# controller.net
KiCad netlist of a schematic drawn in EAGLE
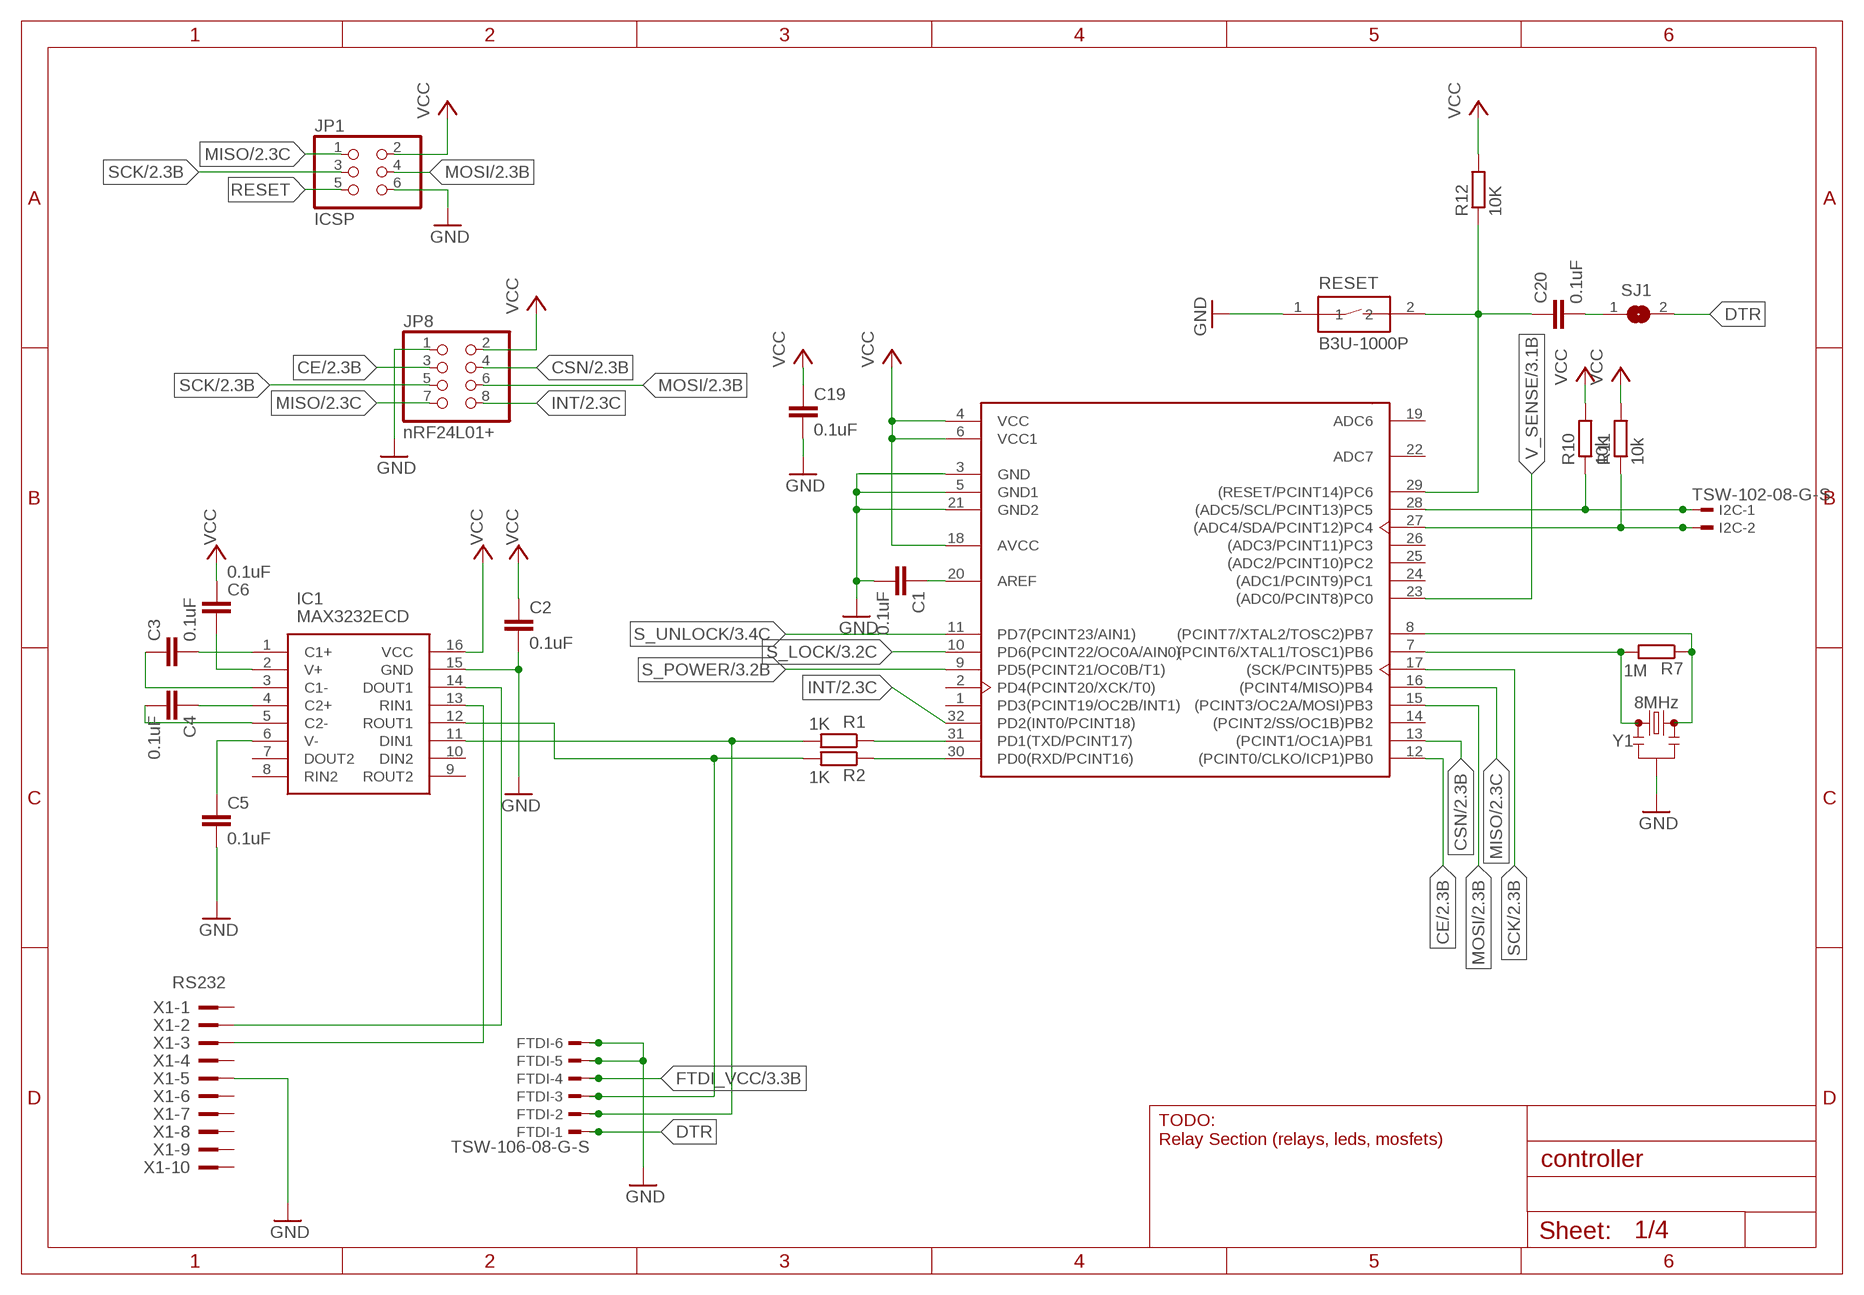
[diagram p0: schematic, sheet 1]
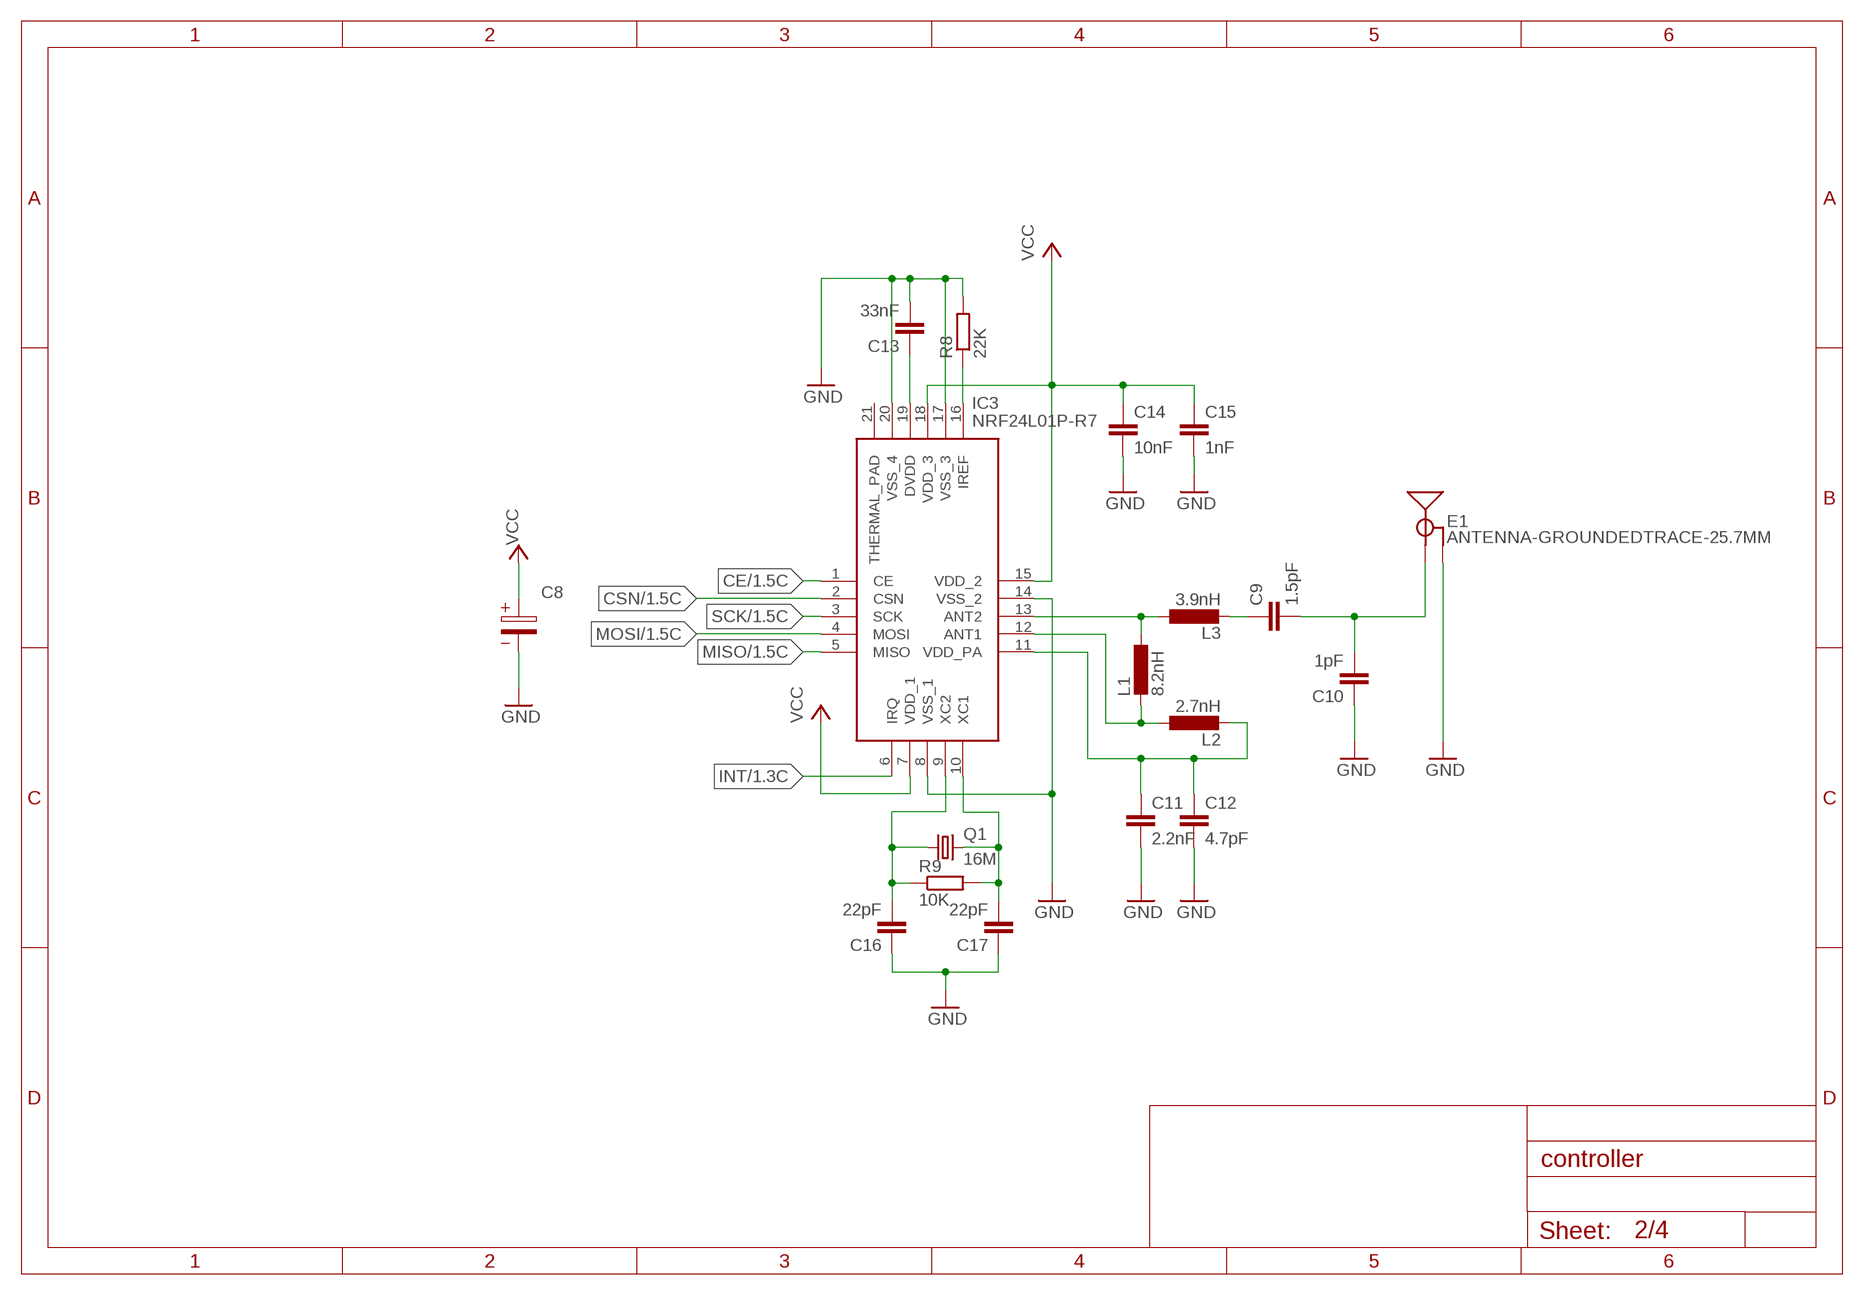
[diagram p1: schematic, sheet 2]
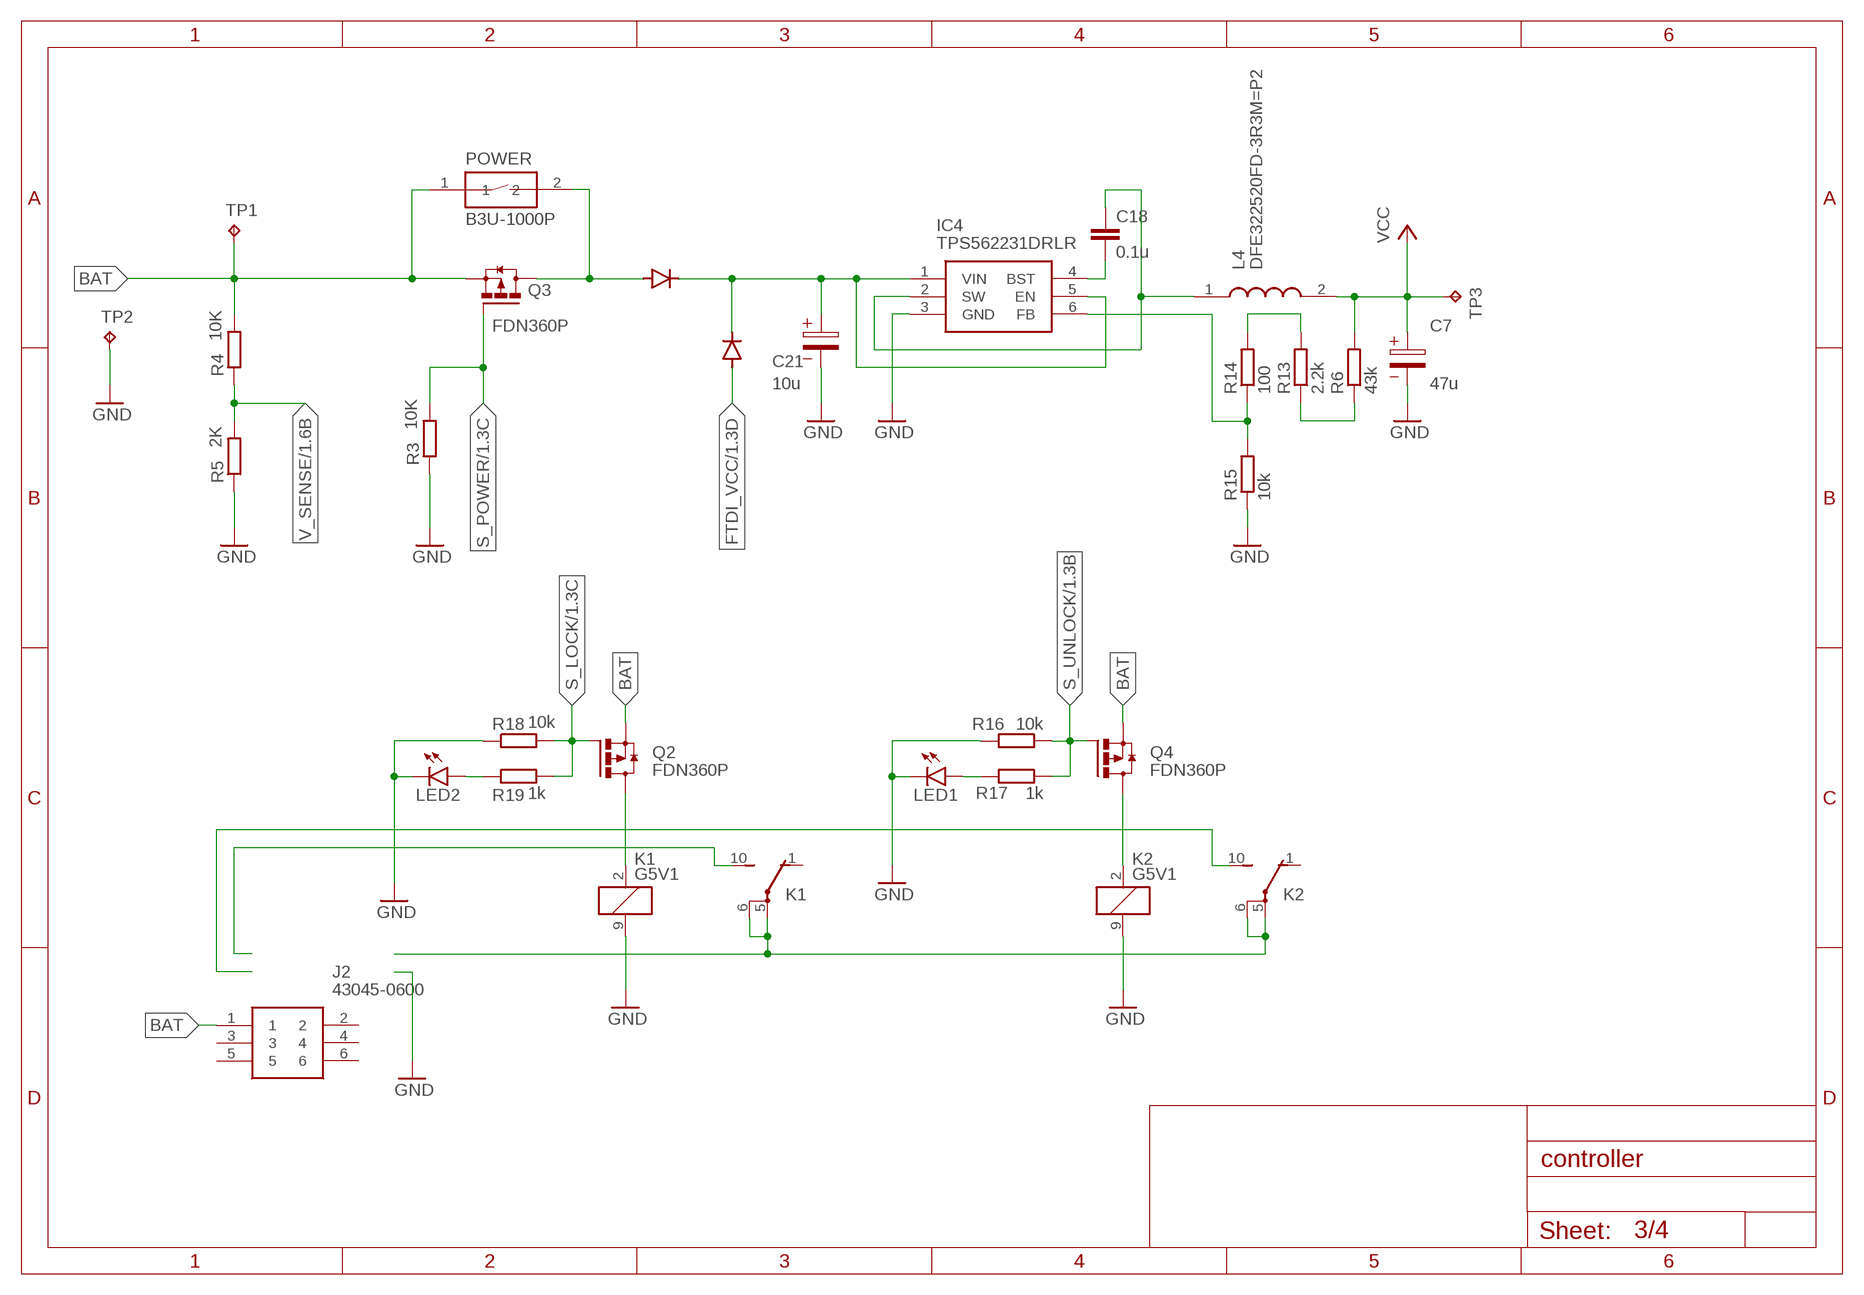
[diagram p2: schematic, sheet 3]
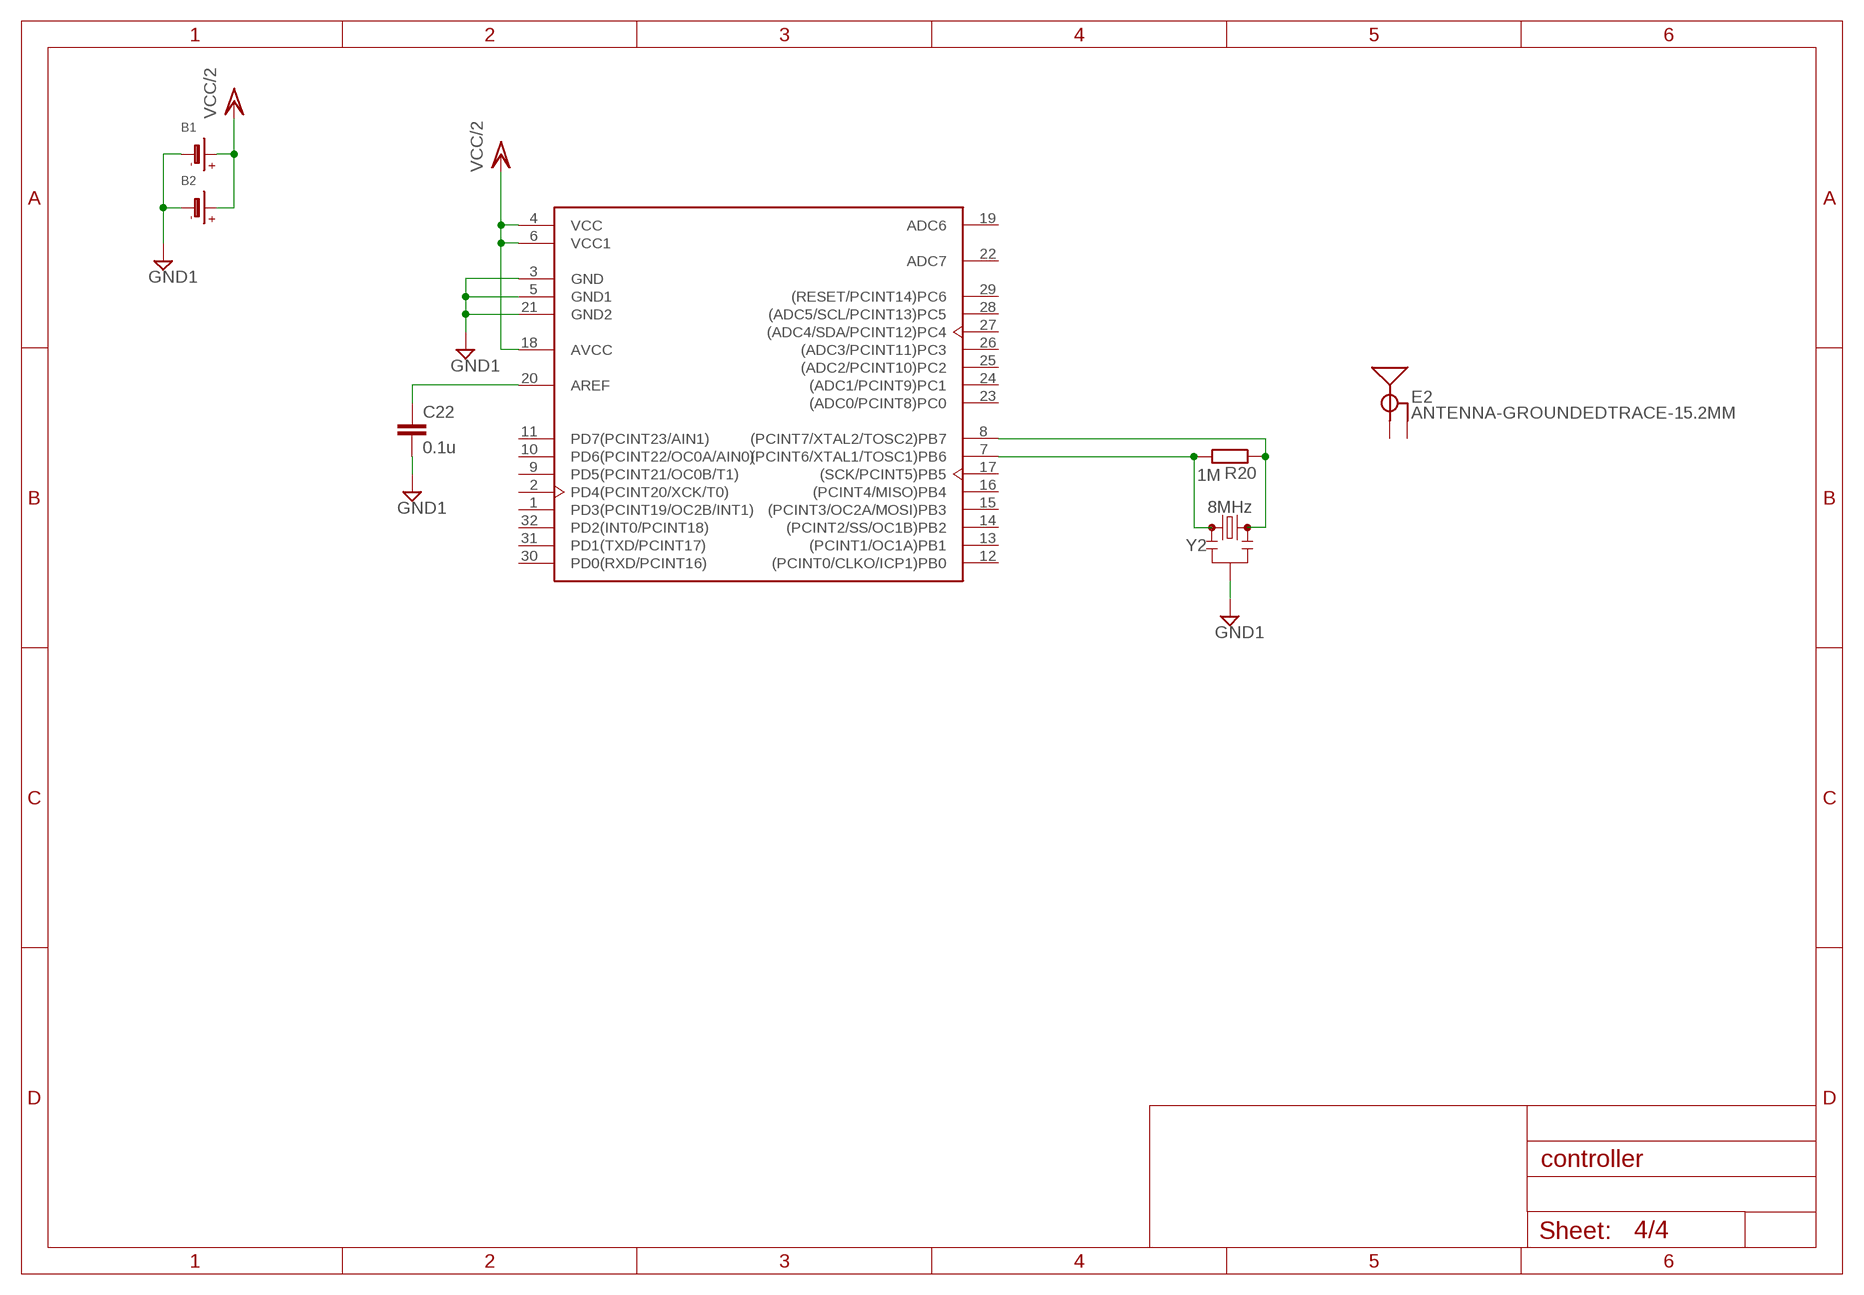
[diagram p3: schematic, sheet 4]

(export (version "E")
  (design (tool "Eeschema 10.0.6"))
  (components
    (comp (ref "B1")
      (value "BATTERYCR2032_BAT-HLD-001")
      (footprint "eagle-import:CR2032_SMT_BAT-HLD-001")
      (libsource (lib "eagle-import") (part "BATTERYCR2032_BAT-HLD-001"))
    )
    (comp (ref "B2")
      (value "BATTERYCR2032_BAT-HLD-001")
      (footprint "eagle-import:CR2032_SMT_BAT-HLD-001")
      (libsource (lib "eagle-import") (part "BATTERYCR2032_BAT-HLD-001"))
    )
    (comp (ref "C22")
      (value "0.1u")
      (footprint "eagle-import:C0805")
      (libsource (lib "eagle-import") (part "C-EUC0805"))
    )
    (comp (ref "E2")
      (value "ANTENNA-GROUNDEDTRACE-15.2MM")
      (footprint "eagle-import:TRACE_ANTENNA_2.4GHZ_15.2MM")
      (libsource (lib "eagle-import") (part "ANTENNA-GROUNDEDTRACE-15.2MM"))
    )
    (comp (ref "R20")
      (value "1M")
      (footprint "eagle-import:R0805")
      (libsource (lib "eagle-import") (part "R-EU_R0805"))
    )
    (comp (ref "U1")
      (value "ATMEGA328P-AU")
      (footprint "eagle-import:TQFP-32")
      (fields
        (field (name "DIGIKEY_PART_NUMBER") "ATMEGA328P-AU-ND")
        (field (name "MANUFACTURER") "Microchip Technology")
        (field (name "CREATED_BY") "PCBLayout.com")
      )
      (libsource (lib "eagle-import") (part "ATMEGA328P-AU"))
    )
    (comp (ref "Y2")
      (value "8MHz")
      (footprint "eagle-import:RESONATOR-SMD-3.2X1.3")
      (libsource (lib "eagle-import") (part "RESONATOR-8MHZSMD_3.2X1.3"))
    )
    (comp (ref "C8")
      (value "WCAP-ASLI_8X6,5_865080149011")
      (footprint "eagle-import:4.2X1.9X2.8(BXCXA)")
      (libsource (lib "eagle-import") (part "WCAP-ASLI_865080149011_8X6,5"))
    )
    (comp (ref "C9")
      (value "1.5pF")
      (footprint "eagle-import:C0805")
      (libsource (lib "eagle-import") (part "resistor_348_C-EUC0805"))
    )
    (comp (ref "C10")
      (value "1pF")
      (footprint "eagle-import:C0805")
      (libsource (lib "eagle-import") (part "resistor_348_C-EUC0805"))
    )
    (comp (ref "C11")
      (value "2.2nF")
      (footprint "eagle-import:C0805")
      (libsource (lib "eagle-import") (part "resistor_348_C-EUC0805"))
    )
    (comp (ref "C12")
      (value "4.7pF")
      (footprint "eagle-import:C0805")
      (libsource (lib "eagle-import") (part "resistor_348_C-EUC0805"))
    )
    (comp (ref "C13")
      (value "33nF")
      (footprint "eagle-import:C0805")
      (libsource (lib "eagle-import") (part "resistor_348_C-EUC0805"))
    )
    (comp (ref "C14")
      (value "10nF")
      (footprint "eagle-import:C0805")
      (libsource (lib "eagle-import") (part "resistor_348_C-EUC0805"))
    )
    (comp (ref "C15")
      (value "1nF")
      (footprint "eagle-import:C0805")
      (libsource (lib "eagle-import") (part "resistor_348_C-EUC0805"))
    )
    (comp (ref "C16")
      (value "22pF")
      (footprint "eagle-import:C0805")
      (libsource (lib "eagle-import") (part "resistor_348_C-EUC0805"))
    )
    (comp (ref "C17")
      (value "22pF")
      (footprint "eagle-import:C0805")
      (libsource (lib "eagle-import") (part "resistor_348_C-EUC0805"))
    )
    (comp (ref "E1")
      (value "ANTENNA-GROUNDEDTRACE-25.7MM")
      (footprint "eagle-import:TRACE_ANTENNA_2.4GHZ_25.7MM")
      (libsource (lib "eagle-import") (part "ANTENNA-GROUNDEDTRACE-25.7MM"))
    )
    (comp (ref "IC3")
      (value "NRF24L01P-R7")
      (footprint "eagle-import:QFN50P400X400X95-21N")
      (fields (field (name "MOUSER_PART_NUMBER") "949-NRF24L01P-R7"))
      (libsource (lib "eagle-import") (part "NRF24L01P-R7"))
    )
    (comp (ref "L1")
      (value "8.2nH")
      (footprint "eagle-import:L2012C")
      (libsource (lib "eagle-import") (part "L-EUL2012C"))
    )
    (comp (ref "L2")
      (value "2.7nH")
      (footprint "eagle-import:L2012C")
      (libsource (lib "eagle-import") (part "L-EUL2012C"))
    )
    (comp (ref "L3")
      (value "3.9nH")
      (footprint "eagle-import:L2012C")
      (libsource (lib "eagle-import") (part "L-EUL2012C"))
    )
    (comp (ref "Q1")
      (value "16M")
      (footprint "eagle-import:HC49_S")
      (libsource (lib "eagle-import") (part "CRYSTALHC49S"))
    )
    (comp (ref "R8")
      (value "22K")
      (footprint "eagle-import:R0805")
      (libsource (lib "eagle-import") (part "R-EU_R0805"))
    )
    (comp (ref "R9")
      (value "10K")
      (footprint "eagle-import:R0805")
      (libsource (lib "eagle-import") (part "R-EU_R0805"))
    )
    (comp (ref "C7")
      (value "47u")
      (footprint "eagle-import:2.6X1.6X1(BXCXA)")
      (libsource (lib "eagle-import") (part "WCAP-ASLI_865080140004_4X5,5"))
    )
    (comp (ref "C18")
      (value "0.1u")
      (footprint "eagle-import:C0805")
      (libsource (lib "eagle-import") (part "C-EUC0805"))
    )
    (comp (ref "C21")
      (value "10u")
      (footprint "eagle-import:2.6X1.6X1(BXCXA)")
      (libsource (lib "eagle-import") (part "WCAP-ASLI_865080340001_4X5,5"))
    )
    (comp (ref "D1")
      (value "DIODE-SOD123")
      (footprint "eagle-import:SOD123")
      (libsource (lib "eagle-import") (part "DIODE-SOD123"))
    )
    (comp (ref "D2")
      (value "DIODE-SOD123")
      (footprint "eagle-import:SOD123")
      (libsource (lib "eagle-import") (part "DIODE-SOD123"))
    )
    (comp (ref "IC4")
      (value "TPS562231DRLR")
      (footprint "eagle-import:SOTFL50P160X60-6N")
      (fields (field (name "MOUSER_PART_NUMBER") "595-TPS562231DRLR"))
      (libsource (lib "eagle-import") (part "TPS562231DRLR"))
    )
    (comp (ref "J2")
      (value "43045-0600")
      (footprint "eagle-import:43045-0600")
      (fields (field (name "MOUSER_PART_NUMBER") "538-43045-0600") (field (name "RS_PART_NUMBER") "2332961P"))
      (libsource (lib "eagle-import") (part "43045-0600"))
    )
    (comp (ref "K1")
      (value "G5V1")
      (footprint "eagle-import:G5V1")
      (fields (field (name "MPN") "G5V-1-DC24"))
      (libsource (lib "eagle-import") (part "G5V1"))
    )
    (comp (ref "K2")
      (value "G5V1")
      (footprint "eagle-import:G5V1")
      (fields (field (name "MPN") "G5V-1-DC24"))
      (libsource (lib "eagle-import") (part "G5V1"))
    )
    (comp (ref "L4")
      (value "DFE322520FD-3R3M=P2")
      (footprint "eagle-import:INDC3225X200N")
      (fields (field (name "MOUSER_PART_NUMBER") "81-DFE322520FD3R3MP2"))
      (libsource (lib "eagle-import") (part "DFE322520FD-3R3M=P2"))
    )
    (comp (ref "LED1")
      (value "LEDCHIPLED_0805")
      (footprint "eagle-import:CHIPLED_0805")
      (libsource (lib "eagle-import") (part "LEDCHIPLED_0805"))
    )
    (comp (ref "LED2")
      (value "LEDCHIPLED_0805")
      (footprint "eagle-import:CHIPLED_0805")
      (libsource (lib "eagle-import") (part "LEDCHIPLED_0805"))
    )
    (comp (ref "POWER")
      (value "B3U-1000P")
      (footprint "eagle-import:B3U-1000P")
      (fields
        (field (name "DIGI_KEY_PART_NUMBER") "SW1020CT-ND")
        (field (name "MANUFACTURER") "Omron Electronics Inc-EMC Div")
        (field (name "CREATED_BY") "PCBLayout.com")
      )
      (libsource (lib "eagle-import") (part "B3U-1000P"))
    )
    (comp (ref "Q2")
      (value "FDN360P")
      (footprint "eagle-import:SUPER-SOT3")
      (libsource (lib "eagle-import") (part "FDN360P"))
    )
    (comp (ref "Q3")
      (value "FDN360P")
      (footprint "eagle-import:SUPER-SOT3")
      (libsource (lib "eagle-import") (part "FDN360P"))
    )
    (comp (ref "Q4")
      (value "FDN360P")
      (footprint "eagle-import:SUPER-SOT3")
      (libsource (lib "eagle-import") (part "FDN360P"))
    )
    (comp (ref "R3")
      (value "10K")
      (footprint "eagle-import:R0805")
      (libsource (lib "eagle-import") (part "R-EU_R0805"))
    )
    (comp (ref "R4")
      (value "10K")
      (footprint "eagle-import:R0805")
      (libsource (lib "eagle-import") (part "R-EU_R0805"))
    )
    (comp (ref "R5")
      (value "2K")
      (footprint "eagle-import:R0805")
      (libsource (lib "eagle-import") (part "R-EU_R0805"))
    )
    (comp (ref "R6")
      (value "43k")
      (footprint "eagle-import:R0805")
      (libsource (lib "eagle-import") (part "R-EU_R0805"))
    )
    (comp (ref "R13")
      (value "2.2k")
      (footprint "eagle-import:R0805")
      (libsource (lib "eagle-import") (part "R-EU_R0805"))
    )
    (comp (ref "R14")
      (value "100")
      (footprint "eagle-import:R0805")
      (libsource (lib "eagle-import") (part "R-EU_R0805"))
    )
    (comp (ref "R15")
      (value "10k")
      (footprint "eagle-import:R0805")
      (libsource (lib "eagle-import") (part "R-EU_R0805"))
    )
    (comp (ref "R16")
      (value "10k")
      (footprint "eagle-import:R0805")
      (libsource (lib "eagle-import") (part "R-EU_R0805"))
    )
    (comp (ref "R17")
      (value "1k")
      (footprint "eagle-import:R0805")
      (libsource (lib "eagle-import") (part "R-EU_R0805"))
    )
    (comp (ref "R18")
      (value "10k")
      (footprint "eagle-import:R0805")
      (libsource (lib "eagle-import") (part "R-EU_R0805"))
    )
    (comp (ref "R19")
      (value "1k")
      (footprint "eagle-import:R0805")
      (libsource (lib "eagle-import") (part "R-EU_R0805"))
    )
    (comp (ref "TP1")
      (value "TPB1,27")
      (footprint "eagle-import:B1,27")
      (libsource (lib "eagle-import") (part "TPB1,27"))
    )
    (comp (ref "TP2")
      (value "TPB1,27")
      (footprint "eagle-import:B1,27")
      (libsource (lib "eagle-import") (part "TPB1,27"))
    )
    (comp (ref "TP3")
      (value "TPB1,27")
      (footprint "eagle-import:B1,27")
      (libsource (lib "eagle-import") (part "TPB1,27"))
    )
    (comp (ref "C1")
      (value "0.1uF")
      (footprint "eagle-import:C0805")
      (libsource (lib "eagle-import") (part "C-EUC0805"))
    )
    (comp (ref "C2")
      (value "0.1uF")
      (footprint "eagle-import:C0805")
      (libsource (lib "eagle-import") (part "C-EUC0805"))
    )
    (comp (ref "C3")
      (value "0.1uF")
      (footprint "eagle-import:C0805")
      (libsource (lib "eagle-import") (part "C-EUC0805"))
    )
    (comp (ref "C4")
      (value "0.1uF")
      (footprint "eagle-import:C0805")
      (libsource (lib "eagle-import") (part "C-EUC0805"))
    )
    (comp (ref "C5")
      (value "0.1uF")
      (footprint "eagle-import:C0805")
      (libsource (lib "eagle-import") (part "C-EUC0805"))
    )
    (comp (ref "C6")
      (value "0.1uF")
      (footprint "eagle-import:C0805")
      (libsource (lib "eagle-import") (part "C-EUC0805"))
    )
    (comp (ref "C19")
      (value "0.1uF")
      (footprint "eagle-import:C0805")
      (libsource (lib "eagle-import") (part "C-EUC0805"))
    )
    (comp (ref "C20")
      (value "0.1uF")
      (footprint "eagle-import:C0805")
      (libsource (lib "eagle-import") (part "C-EUC0805"))
    )
    (comp (ref "FTDI")
      (value "TSW-106-08-G-S")
      (footprint "eagle-import:TSW-106-XX-G-S")
      (fields (field (name "MF") "Samtec Inc.") (field (name "MPN") "TSW-106-07-G-S"))
      (libsource (lib "eagle-import") (part "TSW-106--G-S08"))
    )
    (comp (ref "I2C")
      (value "TSW-102-08-G-S")
      (footprint "eagle-import:TSW-102-XX-G-S")
      (fields (field (name "MF") "Samtec Inc.") (field (name "MPN") "TSW-102-07-G-S"))
      (libsource (lib "eagle-import") (part "TSW-102--G-S08"))
    )
    (comp (ref "IC1")
      (value "MAX3232ECD")
      (footprint "eagle-import:SOIC127P600X175-16N")
      (fields (field (name "MOUSER_PART_NUMBER") "595-MAX3232ECD") (field (name "RS_PART_NUMBER") "6608704P"))
      (libsource (lib "eagle-import") (part "MAX3232ECD"))
    )
    (comp (ref "JP1")
      (value "ICSP")
      (footprint "eagle-import:2X03")
      (libsource (lib "eagle-import") (part "PINHD-2X3"))
    )
    (comp (ref "JP8")
      (value "nRF24L01+")
      (footprint "eagle-import:2X04")
      (libsource (lib "eagle-import") (part "PINHD-2X4"))
    )
    (comp (ref "R1")
      (value "1K")
      (footprint "eagle-import:R0805")
      (libsource (lib "eagle-import") (part "R-EU_R0805"))
    )
    (comp (ref "R2")
      (value "1K")
      (footprint "eagle-import:R0805")
      (libsource (lib "eagle-import") (part "R-EU_R0805"))
    )
    (comp (ref "R7")
      (value "1M")
      (footprint "eagle-import:R0805")
      (libsource (lib "eagle-import") (part "R-EU_R0805"))
    )
    (comp (ref "R10")
      (value "10k")
      (footprint "eagle-import:R0805")
      (libsource (lib "eagle-import") (part "R-EU_R0805"))
    )
    (comp (ref "R11")
      (value "10k")
      (footprint "eagle-import:R0805")
      (libsource (lib "eagle-import") (part "R-EU_R0805"))
    )
    (comp (ref "R12")
      (value "10K")
      (footprint "eagle-import:R0805")
      (libsource (lib "eagle-import") (part "R-EU_R0805"))
    )
    (comp (ref "RESET")
      (value "B3U-1000P")
      (footprint "eagle-import:B3U-1000P")
      (fields
        (field (name "DIGI_KEY_PART_NUMBER") "SW1020CT-ND")
        (field (name "MANUFACTURER") "Omron Electronics Inc-EMC Div")
        (field (name "CREATED_BY") "PCBLayout.com")
      )
      (libsource (lib "eagle-import") (part "B3U-1000P"))
    )
    (comp (ref "SJ1") (value "SJ") (footprint "eagle-import:SJ") (libsource (lib "eagle-import") (part "SJ")))
    (comp (ref "U2")
      (value "ATMEGA328P-AU")
      (footprint "eagle-import:TQFP-32")
      (fields
        (field (name "DIGIKEY_PART_NUMBER") "ATMEGA328P-AU-ND")
        (field (name "MANUFACTURER") "Microchip Technology")
        (field (name "CREATED_BY") "PCBLayout.com")
      )
      (libsource (lib "eagle-import") (part "ATMEGA328P-AU"))
    )
    (comp (ref "X1")
      (value "RS232")
      (footprint "eagle-import:PAK100_2500-10")
      (fields (field (name "MF") "3M") (field (name "MPN") "2510-6002UB"))
      (libsource (lib "eagle-import") (part "2510-"))
    )
    (comp (ref "Y1")
      (value "8MHz")
      (footprint "eagle-import:RESONATOR-SMD-3.2X1.3")
      (libsource (lib "eagle-import") (part "RESONATOR-8MHZSMD_3.2X1.3"))
    )
  )
  (nets
    (net (code "1") (name "BAT") (class "Default")
      (node (ref "J2") (pin "1") (pinfunction "1_1") (pintype "bidirectional"))
      (node (ref "POWER") (pin "1") (pinfunction "1_1") (pintype "passive"))
      (node (ref "Q2") (pin "2") (pinfunction "S_2") (pintype "passive"))
      (node (ref "Q3") (pin "2") (pinfunction "S_2") (pintype "passive"))
      (node (ref "Q4") (pin "2") (pinfunction "S_2") (pintype "passive"))
      (node (ref "R4") (pin "2") (pinfunction "2_2") (pintype "passive"))
      (node (ref "TP1") (pin "TP") (pinfunction "TP_TP") (pintype "input"))
    )
    (net (code "2") (name "CE") (class "Default")
      (node (ref "IC3") (pin "1") (pinfunction "CE_1") (pintype "bidirectional"))
      (node (ref "JP8") (pin "3") (pinfunction "3_3") (pintype "passive"))
      (node (ref "U2") (pin "12") (pinfunction "(PCINT0/CLKO/ICP1)PB0_12") (pintype "bidirectional"))
    )
    (net (code "3") (name "CSN") (class "Default")
      (node (ref "IC3") (pin "2") (pinfunction "CSN_2") (pintype "bidirectional"))
      (node (ref "JP8") (pin "4") (pinfunction "4_4") (pintype "passive"))
      (node (ref "U2") (pin "13") (pinfunction "(PCINT1/OC1A)PB1_13") (pintype "bidirectional"))
    )
    (net (code "4") (name "DTR") (class "Default")
      (node (ref "FTDI") (pin "1") (pinfunction "1_1") (pintype "passive"))
      (node (ref "SJ1") (pin "2") (pinfunction "2_2") (pintype "passive"))
    )
    (net (code "5") (name "FTDI_VCC") (class "Default")
      (node (ref "D1") (pin "A") (pinfunction "A_A") (pintype "passive"))
      (node (ref "FTDI") (pin "4") (pinfunction "1_4") (pintype "passive"))
    )
    (net (code "6") (name "GND") (class "Default")
      (node (ref "C1") (pin "2") (pinfunction "2_2") (pintype "passive"))
      (node (ref "C10") (pin "1") (pinfunction "1_1") (pintype "passive"))
      (node (ref "C11") (pin "2") (pinfunction "2_2") (pintype "passive"))
      (node (ref "C12") (pin "2") (pinfunction "2_2") (pintype "passive"))
      (node (ref "C13") (pin "2") (pinfunction "2_2") (pintype "passive"))
      (node (ref "C14") (pin "2") (pinfunction "2_2") (pintype "passive"))
      (node (ref "C15") (pin "2") (pinfunction "2_2") (pintype "passive"))
      (node (ref "C16") (pin "1") (pinfunction "1_1") (pintype "passive"))
      (node (ref "C17") (pin "1") (pinfunction "1_1") (pintype "passive"))
      (node (ref "C19") (pin "2") (pinfunction "2_2") (pintype "passive"))
      (node (ref "C2") (pin "2") (pinfunction "2_2") (pintype "passive"))
      (node (ref "C21") (pin "2") (pinfunction "2_2") (pintype "passive"))
      (node (ref "C5") (pin "2") (pinfunction "2_2") (pintype "passive"))
      (node (ref "C7") (pin "2") (pinfunction "2_2") (pintype "passive"))
      (node (ref "C8") (pin "2") (pinfunction "2_2") (pintype "passive"))
      (node (ref "E1") (pin "GND") (pinfunction "GND_GND") (pintype "bidirectional"))
      (node (ref "E1") (pin "GND2") (pinfunction "GND_GND2") (pintype "bidirectional"))
      (node (ref "FTDI") (pin "5") (pinfunction "1_5") (pintype "passive"))
      (node (ref "FTDI") (pin "6") (pinfunction "1_6") (pintype "passive"))
      (node (ref "IC1") (pin "15") (pinfunction "GND_15") (pintype "bidirectional"))
      (node (ref "IC3") (pin "14") (pinfunction "VSS_2_14") (pintype "bidirectional"))
      (node (ref "IC3") (pin "17") (pinfunction "VSS_3_17") (pintype "bidirectional"))
      (node (ref "IC3") (pin "20") (pinfunction "VSS_4_20") (pintype "bidirectional"))
      (node (ref "IC3") (pin "8") (pinfunction "VSS_1_8") (pintype "bidirectional"))
      (node (ref "IC4") (pin "3") (pinfunction "GND_3") (pintype "bidirectional"))
      (node (ref "JP1") (pin "6") (pinfunction "6_6") (pintype "passive"))
      (node (ref "JP8") (pin "1") (pinfunction "1_1") (pintype "passive"))
      (node (ref "K1") (pin "9") (pinfunction "2_9") (pintype "passive"))
      (node (ref "K2") (pin "9") (pinfunction "2_9") (pintype "passive"))
      (node (ref "LED1") (pin "C") (pinfunction "C_C") (pintype "passive"))
      (node (ref "LED2") (pin "C") (pinfunction "C_C") (pintype "passive"))
      (node (ref "R15") (pin "1") (pinfunction "1_1") (pintype "passive"))
      (node (ref "R16") (pin "2") (pinfunction "2_2") (pintype "passive"))
      (node (ref "R18") (pin "1") (pinfunction "1_1") (pintype "passive"))
      (node (ref "R3") (pin "1") (pinfunction "1_1") (pintype "passive"))
      (node (ref "R5") (pin "1") (pinfunction "1_1") (pintype "passive"))
      (node (ref "R8") (pin "2") (pinfunction "2_2") (pintype "passive"))
      (node (ref "RESET") (pin "1") (pinfunction "1_1") (pintype "passive"))
      (node (ref "TP2") (pin "TP") (pinfunction "TP_TP") (pintype "input"))
      (node (ref "U2") (pin "21") (pinfunction "GND2_21") (pintype "power_in"))
      (node (ref "U2") (pin "3") (pinfunction "GND_3") (pintype "power_in"))
      (node (ref "U2") (pin "5") (pinfunction "GND1_5") (pintype "power_in"))
      (node (ref "X1") (pin "5") (pinfunction "KL_5") (pintype "passive"))
      (node (ref "Y1") (pin "2") (pinfunction "2_2") (pintype "passive"))
    )
    (net (code "7") (name "GND1") (class "Default")
      (node (ref "B1") (pin "-") (pinfunction "-_-") (pintype "passive"))
      (node (ref "B2") (pin "-") (pinfunction "-_-") (pintype "passive"))
      (node (ref "C22") (pin "2") (pinfunction "2_2") (pintype "passive"))
      (node (ref "U1") (pin "21") (pinfunction "GND2_21") (pintype "power_in"))
      (node (ref "U1") (pin "3") (pinfunction "GND_3") (pintype "power_in"))
      (node (ref "U1") (pin "5") (pinfunction "GND1_5") (pintype "power_in"))
      (node (ref "Y2") (pin "2") (pinfunction "2_2") (pintype "passive"))
    )
    (net (code "8") (name "INT") (class "Default")
      (node (ref "IC3") (pin "6") (pinfunction "IRQ_6") (pintype "bidirectional"))
      (node (ref "JP8") (pin "8") (pinfunction "8_8") (pintype "passive"))
      (node (ref "U2") (pin "32") (pinfunction "PD2(INT0/PCINT18)_32") (pintype "bidirectional"))
    )
    (net (code "9") (name "MISO") (class "Default")
      (node (ref "IC3") (pin "5") (pinfunction "MISO_5") (pintype "bidirectional"))
      (node (ref "JP1") (pin "1") (pinfunction "1_1") (pintype "passive"))
      (node (ref "JP8") (pin "7") (pinfunction "7_7") (pintype "passive"))
      (node (ref "U2") (pin "16") (pinfunction "(PCINT4/MISO)PB4_16") (pintype "bidirectional"))
    )
    (net (code "10") (name "MOSI") (class "Default")
      (node (ref "IC3") (pin "4") (pinfunction "MOSI_4") (pintype "bidirectional"))
      (node (ref "JP1") (pin "4") (pinfunction "4_4") (pintype "passive"))
      (node (ref "JP8") (pin "6") (pinfunction "6_6") (pintype "passive"))
      (node (ref "U2") (pin "15") (pinfunction "(PCINT3/OC2A/MOSI)PB3_15") (pintype "bidirectional"))
    )
    (net (code "11") (name "Net-(C9-Pad1)") (class "Default")
      (node (ref "C9") (pin "1") (pinfunction "1_1") (pintype "passive"))
      (node (ref "L3") (pin "2") (pinfunction "2_2") (pintype "passive"))
    )
    (net (code "12") (name "Net-(C20-Pad2)") (class "Default")
      (node (ref "C20") (pin "2") (pinfunction "2_2") (pintype "passive"))
      (node (ref "SJ1") (pin "1") (pinfunction "1_1") (pintype "passive"))
    )
    (net (code "13") (name "Net-(E1-SIGNAL)") (class "Default")
      (node (ref "C10") (pin "2") (pinfunction "2_2") (pintype "passive"))
      (node (ref "C9") (pin "2") (pinfunction "2_2") (pintype "passive"))
      (node (ref "E1") (pin "ANT") (pinfunction "SIGNAL_ANT") (pintype "bidirectional"))
    )
    (net (code "14") (name "Net-(FTDIB-1)") (class "Default")
      (node (ref "FTDI") (pin "2") (pinfunction "1_2") (pintype "passive"))
      (node (ref "IC1") (pin "11") (pinfunction "DIN1_11") (pintype "bidirectional"))
      (node (ref "R1") (pin "2") (pinfunction "2_2") (pintype "passive"))
    )
    (net (code "15") (name "Net-(FTDIC-1)") (class "Default")
      (node (ref "FTDI") (pin "3") (pinfunction "1_3") (pintype "passive"))
      (node (ref "IC1") (pin "12") (pinfunction "ROUT1_12") (pintype "bidirectional"))
      (node (ref "R2") (pin "2") (pinfunction "2_2") (pintype "passive"))
    )
    (net (code "16") (name "Net-(I2CB-1)") (class "Default")
      (node (ref "I2C") (pin "2") (pinfunction "1_2") (pintype "passive"))
      (node (ref "R11") (pin "1") (pinfunction "1_1") (pintype "passive"))
      (node (ref "U2") (pin "27") (pinfunction "(ADC4/SDA/PCINT12)PC4_27") (pintype "bidirectional"))
    )
    (net (code "17") (name "Net-(IC1-C1+)") (class "Default")
      (node (ref "C3") (pin "2") (pinfunction "2_2") (pintype "passive"))
      (node (ref "IC1") (pin "1") (pinfunction "C1+_1") (pintype "bidirectional"))
    )
    (net (code "18") (name "Net-(IC1-C1-)") (class "Default")
      (node (ref "C3") (pin "1") (pinfunction "1_1") (pintype "passive"))
      (node (ref "IC1") (pin "3") (pinfunction "C1-_3") (pintype "bidirectional"))
    )
    (net (code "19") (name "Net-(IC1-C2+)") (class "Default")
      (node (ref "C4") (pin "1") (pinfunction "1_1") (pintype "passive"))
      (node (ref "IC1") (pin "4") (pinfunction "C2+_4") (pintype "bidirectional"))
    )
    (net (code "20") (name "Net-(IC1-C2-)") (class "Default")
      (node (ref "C4") (pin "2") (pinfunction "2_2") (pintype "passive"))
      (node (ref "IC1") (pin "5") (pinfunction "C2-_5") (pintype "bidirectional"))
    )
    (net (code "21") (name "Net-(IC1-DOUT1)") (class "Default")
      (node (ref "IC1") (pin "14") (pinfunction "DOUT1_14") (pintype "bidirectional"))
      (node (ref "X1") (pin "2") (pinfunction "KL_2") (pintype "passive"))
    )
    (net (code "22") (name "Net-(IC1-RIN1)") (class "Default")
      (node (ref "IC1") (pin "13") (pinfunction "RIN1_13") (pintype "bidirectional"))
      (node (ref "X1") (pin "3") (pinfunction "KL_3") (pintype "passive"))
    )
    (net (code "23") (name "Net-(IC1-V+)") (class "Default")
      (node (ref "C6") (pin "1") (pinfunction "1_1") (pintype "passive"))
      (node (ref "IC1") (pin "2") (pinfunction "V+_2") (pintype "bidirectional"))
    )
    (net (code "24") (name "Net-(IC1-V-)") (class "Default")
      (node (ref "C5") (pin "1") (pinfunction "1_1") (pintype "passive"))
      (node (ref "IC1") (pin "6") (pinfunction "V-_6") (pintype "bidirectional"))
    )
    (net (code "25") (name "Net-(IC3-ANT1)") (class "Default")
      (node (ref "IC3") (pin "12") (pinfunction "ANT1_12") (pintype "bidirectional"))
      (node (ref "L1") (pin "2") (pinfunction "2_2") (pintype "passive"))
      (node (ref "L2") (pin "1") (pinfunction "1_1") (pintype "passive"))
    )
    (net (code "26") (name "Net-(IC3-ANT2)") (class "Default")
      (node (ref "IC3") (pin "13") (pinfunction "ANT2_13") (pintype "bidirectional"))
      (node (ref "L1") (pin "1") (pinfunction "1_1") (pintype "passive"))
      (node (ref "L3") (pin "1") (pinfunction "1_1") (pintype "passive"))
    )
    (net (code "27") (name "Net-(IC3-DVDD)") (class "Default")
      (node (ref "C13") (pin "1") (pinfunction "1_1") (pintype "passive"))
      (node (ref "IC3") (pin "19") (pinfunction "DVDD_19") (pintype "bidirectional"))
    )
    (net (code "28") (name "Net-(IC3-IREF)") (class "Default")
      (node (ref "IC3") (pin "16") (pinfunction "IREF_16") (pintype "bidirectional"))
      (node (ref "R8") (pin "1") (pinfunction "1_1") (pintype "passive"))
    )
    (net (code "29") (name "Net-(IC3-VDD_PA)") (class "Default")
      (node (ref "C11") (pin "1") (pinfunction "1_1") (pintype "passive"))
      (node (ref "C12") (pin "1") (pinfunction "1_1") (pintype "passive"))
      (node (ref "IC3") (pin "11") (pinfunction "VDD_PA_11") (pintype "bidirectional"))
      (node (ref "L2") (pin "2") (pinfunction "2_2") (pintype "passive"))
    )
    (net (code "30") (name "Net-(IC3-XC1)") (class "Default")
      (node (ref "C17") (pin "2") (pinfunction "2_2") (pintype "passive"))
      (node (ref "IC3") (pin "10") (pinfunction "XC1_10") (pintype "bidirectional"))
      (node (ref "Q1") (pin "2") (pinfunction "2_2") (pintype "passive"))
      (node (ref "R9") (pin "2") (pinfunction "2_2") (pintype "passive"))
    )
    (net (code "31") (name "Net-(IC3-XC2)") (class "Default")
      (node (ref "C16") (pin "2") (pinfunction "2_2") (pintype "passive"))
      (node (ref "IC3") (pin "9") (pinfunction "XC2_9") (pintype "bidirectional"))
      (node (ref "Q1") (pin "1") (pinfunction "1_1") (pintype "passive"))
      (node (ref "R9") (pin "1") (pinfunction "1_1") (pintype "passive"))
    )
    (net (code "32") (name "Net-(IC4-BST)") (class "Default")
      (node (ref "C18") (pin "2") (pinfunction "2_2") (pintype "passive"))
      (node (ref "IC4") (pin "4") (pinfunction "BST_4") (pintype "bidirectional"))
    )
    (net (code "33") (name "Net-(IC4-EN)") (class "Default")
      (node (ref "C21") (pin "1") (pinfunction "1_1") (pintype "passive"))
      (node (ref "D1") (pin "C") (pinfunction "C_C") (pintype "passive"))
      (node (ref "D2") (pin "C") (pinfunction "C_C") (pintype "passive"))
      (node (ref "IC4") (pin "1") (pinfunction "VIN_1") (pintype "bidirectional"))
      (node (ref "IC4") (pin "5") (pinfunction "EN_5") (pintype "bidirectional"))
    )
    (net (code "34") (name "Net-(IC4-FB)") (class "Default")
      (node (ref "IC4") (pin "6") (pinfunction "FB_6") (pintype "bidirectional"))
      (node (ref "R14") (pin "1") (pinfunction "1_1") (pintype "passive"))
      (node (ref "R15") (pin "2") (pinfunction "2_2") (pintype "passive"))
    )
    (net (code "35") (name "Net-(IC4-SW)") (class "Default")
      (node (ref "C18") (pin "1") (pinfunction "1_1") (pintype "passive"))
      (node (ref "IC4") (pin "2") (pinfunction "SW_2") (pintype "bidirectional"))
      (node (ref "L4") (pin "1") (pinfunction "1_1") (pintype "bidirectional"))
    )
    (net (code "36") (name "Net-(K1A-1)") (class "Default")
      (node (ref "K1") (pin "2") (pinfunction "1_2") (pintype "passive"))
      (node (ref "Q2") (pin "3") (pinfunction "D_3") (pintype "passive"))
    )
    (net (code "37") (name "Net-(K1B-P-Pad5)") (class "Default")
      (node (ref "K1") (pin "5") (pinfunction "P_5") (pintype "passive"))
      (node (ref "K1") (pin "6") (pinfunction "P_6") (pintype "passive"))
      (node (ref "K2") (pin "5") (pinfunction "P_5") (pintype "passive"))
      (node (ref "K2") (pin "6") (pinfunction "P_6") (pintype "passive"))
    )
    (net (code "38") (name "Net-(K2A-1)") (class "Default")
      (node (ref "K2") (pin "2") (pinfunction "1_2") (pintype "passive"))
      (node (ref "Q4") (pin "3") (pinfunction "D_3") (pintype "passive"))
    )
    (net (code "39") (name "Net-(LED1-PadA)") (class "Default")
      (node (ref "LED1") (pin "A") (pinfunction "A_A") (pintype "passive"))
      (node (ref "R17") (pin "2") (pinfunction "2_2") (pintype "passive"))
    )
    (net (code "40") (name "Net-(LED2-PadA)") (class "Default")
      (node (ref "LED2") (pin "A") (pinfunction "A_A") (pintype "passive"))
      (node (ref "R19") (pin "1") (pinfunction "1_1") (pintype "passive"))
    )
    (net (code "41") (name "Net-(Q3-D)") (class "Default")
      (node (ref "D2") (pin "A") (pinfunction "A_A") (pintype "passive"))
      (node (ref "POWER") (pin "2") (pinfunction "2_2") (pintype "passive"))
      (node (ref "Q3") (pin "3") (pinfunction "D_3") (pintype "passive"))
    )
    (net (code "42") (name "Net-(R13-Pad1)") (class "Default")
      (node (ref "R13") (pin "1") (pinfunction "1_1") (pintype "passive"))
      (node (ref "R6") (pin "1") (pinfunction "1_1") (pintype "passive"))
    )
    (net (code "43") (name "Net-(R13-Pad2)") (class "Default")
      (node (ref "R13") (pin "2") (pinfunction "2_2") (pintype "passive"))
      (node (ref "R14") (pin "2") (pinfunction "2_2") (pintype "passive"))
    )
    (net (code "44") (name "Net-(U1-(PCINT6{slash}XTAL1{slash}TOSC1)PB6)") (class "Default")
      (node (ref "R20") (pin "2") (pinfunction "2_2") (pintype "passive"))
      (node (ref "U1") (pin "7") (pinfunction "(PCINT6/XTAL1/TOSC1)PB6_7") (pintype "bidirectional"))
      (node (ref "Y2") (pin "1") (pinfunction "1_1") (pintype "passive"))
    )
    (net (code "45") (name "Net-(U1-(PCINT7{slash}XTAL2{slash}TOSC2)PB7)") (class "Default")
      (node (ref "R20") (pin "1") (pinfunction "1_1") (pintype "passive"))
      (node (ref "U1") (pin "8") (pinfunction "(PCINT7/XTAL2/TOSC2)PB7_8") (pintype "bidirectional"))
      (node (ref "Y2") (pin "3") (pinfunction "3_3") (pintype "passive"))
    )
    (net (code "46") (name "Net-(U1-AREF)") (class "Default")
      (node (ref "C22") (pin "1") (pinfunction "1_1") (pintype "passive"))
      (node (ref "U1") (pin "20") (pinfunction "AREF_20") (pintype "power_in"))
    )
    (net (code "47") (name "Net-(U2-(ADC5{slash}SCL{slash}PCINT13)PC5)") (class "Default")
      (node (ref "I2C") (pin "1") (pinfunction "1_1") (pintype "passive"))
      (node (ref "R10") (pin "1") (pinfunction "1_1") (pintype "passive"))
      (node (ref "U2") (pin "28") (pinfunction "(ADC5/SCL/PCINT13)PC5_28") (pintype "bidirectional"))
    )
    (net (code "48") (name "Net-(U2-(PCINT6{slash}XTAL1{slash}TOSC1)PB6)") (class "Default")
      (node (ref "R7") (pin "2") (pinfunction "2_2") (pintype "passive"))
      (node (ref "U2") (pin "7") (pinfunction "(PCINT6/XTAL1/TOSC1)PB6_7") (pintype "bidirectional"))
      (node (ref "Y1") (pin "1") (pinfunction "1_1") (pintype "passive"))
    )
    (net (code "49") (name "Net-(U2-(PCINT7{slash}XTAL2{slash}TOSC2)PB7)") (class "Default")
      (node (ref "R7") (pin "1") (pinfunction "1_1") (pintype "passive"))
      (node (ref "U2") (pin "8") (pinfunction "(PCINT7/XTAL2/TOSC2)PB7_8") (pintype "bidirectional"))
      (node (ref "Y1") (pin "3") (pinfunction "3_3") (pintype "passive"))
    )
    (net (code "50") (name "Net-(U2-AREF)") (class "Default")
      (node (ref "C1") (pin "1") (pinfunction "1_1") (pintype "passive"))
      (node (ref "U2") (pin "20") (pinfunction "AREF_20") (pintype "power_in"))
    )
    (net (code "51") (name "Net-(U2-PD0(RXD{slash}PCINT16))") (class "Default")
      (node (ref "R2") (pin "1") (pinfunction "1_1") (pintype "passive"))
      (node (ref "U2") (pin "30") (pinfunction "PD0(RXD/PCINT16)_30") (pintype "bidirectional"))
    )
    (net (code "52") (name "Net-(U2-PD1(TXD{slash}PCINT17))") (class "Default")
      (node (ref "R1") (pin "1") (pinfunction "1_1") (pintype "passive"))
      (node (ref "U2") (pin "31") (pinfunction "PD1(TXD/PCINT17)_31") (pintype "bidirectional"))
    )
    (net (code "53") (name "RESET") (class "Default")
      (node (ref "C20") (pin "1") (pinfunction "1_1") (pintype "passive"))
      (node (ref "JP1") (pin "5") (pinfunction "5_5") (pintype "passive"))
      (node (ref "R12") (pin "1") (pinfunction "1_1") (pintype "passive"))
      (node (ref "RESET") (pin "2") (pinfunction "2_2") (pintype "passive"))
      (node (ref "U2") (pin "29") (pinfunction "(RESET/PCINT14)PC6_29") (pintype "bidirectional"))
    )
    (net (code "54") (name "SCK") (class "Default")
      (node (ref "IC3") (pin "3") (pinfunction "SCK_3") (pintype "bidirectional"))
      (node (ref "JP1") (pin "3") (pinfunction "3_3") (pintype "passive"))
      (node (ref "JP8") (pin "5") (pinfunction "5_5") (pintype "passive"))
      (node (ref "U2") (pin "17") (pinfunction "(SCK/PCINT5)PB5_17") (pintype "bidirectional"))
    )
    (net (code "55") (name "S_LOCK") (class "Default")
      (node (ref "Q2") (pin "1") (pinfunction "G_1") (pintype "passive"))
      (node (ref "R18") (pin "2") (pinfunction "2_2") (pintype "passive"))
      (node (ref "R19") (pin "2") (pinfunction "2_2") (pintype "passive"))
      (node (ref "U2") (pin "10") (pinfunction "PD6(PCINT22/OC0A/AIN0)_10") (pintype "bidirectional"))
    )
    (net (code "56") (name "S_POWER") (class "Default")
      (node (ref "Q3") (pin "1") (pinfunction "G_1") (pintype "passive"))
      (node (ref "R3") (pin "2") (pinfunction "2_2") (pintype "passive"))
      (node (ref "U2") (pin "9") (pinfunction "PD5(PCINT21/OC0B/T1)_9") (pintype "bidirectional"))
    )
    (net (code "57") (name "S_UNLOCK") (class "Default")
      (node (ref "Q4") (pin "1") (pinfunction "G_1") (pintype "passive"))
      (node (ref "R16") (pin "1") (pinfunction "1_1") (pintype "passive"))
      (node (ref "R17") (pin "1") (pinfunction "1_1") (pintype "passive"))
      (node (ref "U2") (pin "11") (pinfunction "PD7(PCINT23/AIN1)_11") (pintype "bidirectional"))
    )
    (net (code "58") (name "VCC") (class "Default")
      (node (ref "C14") (pin "1") (pinfunction "1_1") (pintype "passive"))
      (node (ref "C15") (pin "1") (pinfunction "1_1") (pintype "passive"))
      (node (ref "C19") (pin "1") (pinfunction "1_1") (pintype "passive"))
      (node (ref "C2") (pin "1") (pinfunction "1_1") (pintype "passive"))
      (node (ref "C6") (pin "2") (pinfunction "2_2") (pintype "passive"))
      (node (ref "C7") (pin "1") (pinfunction "1_1") (pintype "passive"))
      (node (ref "C8") (pin "1") (pinfunction "1_1") (pintype "passive"))
      (node (ref "IC1") (pin "16") (pinfunction "VCC_16") (pintype "bidirectional"))
      (node (ref "IC3") (pin "15") (pinfunction "VDD_2_15") (pintype "bidirectional"))
      (node (ref "IC3") (pin "18") (pinfunction "VDD_3_18") (pintype "bidirectional"))
      (node (ref "IC3") (pin "7") (pinfunction "VDD_1_7") (pintype "bidirectional"))
      (node (ref "JP1") (pin "2") (pinfunction "2_2") (pintype "passive"))
      (node (ref "JP8") (pin "2") (pinfunction "2_2") (pintype "passive"))
      (node (ref "L4") (pin "2") (pinfunction "2_2") (pintype "bidirectional"))
      (node (ref "R10") (pin "2") (pinfunction "2_2") (pintype "passive"))
      (node (ref "R11") (pin "2") (pinfunction "2_2") (pintype "passive"))
      (node (ref "R12") (pin "2") (pinfunction "2_2") (pintype "passive"))
      (node (ref "R6") (pin "2") (pinfunction "2_2") (pintype "passive"))
      (node (ref "TP3") (pin "TP") (pinfunction "TP_TP") (pintype "input"))
      (node (ref "U2") (pin "18") (pinfunction "AVCC_18") (pintype "power_in"))
      (node (ref "U2") (pin "4") (pinfunction "VCC_4") (pintype "power_in"))
      (node (ref "U2") (pin "6") (pinfunction "VCC1_6") (pintype "power_in"))
    )
    (net (code "59") (name "VCC{slash}2") (class "Default")
      (node (ref "B1") (pin "+$1") (pinfunction "+_+$1") (pintype "passive"))
      (node (ref "B1") (pin "+$2") (pinfunction "+_+$2") (pintype "passive"))
      (node (ref "B2") (pin "+$1") (pinfunction "+_+$1") (pintype "passive"))
      (node (ref "B2") (pin "+$2") (pinfunction "+_+$2") (pintype "passive"))
      (node (ref "U1") (pin "18") (pinfunction "AVCC_18") (pintype "power_in"))
      (node (ref "U1") (pin "4") (pinfunction "VCC_4") (pintype "power_in"))
      (node (ref "U1") (pin "6") (pinfunction "VCC1_6") (pintype "power_in"))
    )
    (net (code "60") (name "V_SENSE") (class "Default")
      (node (ref "R4") (pin "1") (pinfunction "1_1") (pintype "passive"))
      (node (ref "R5") (pin "2") (pinfunction "2_2") (pintype "passive"))
      (node (ref "U2") (pin "23") (pinfunction "(ADC0/PCINT8)PC0_23") (pintype "bidirectional"))
    )
    (net (code "61") (name "unconnected-(E2-PadGND)") (class "Default")
      (node (ref "E2") (pin "GND") (pinfunction "GND_GND") (pintype "bidirectional"))
    )
    (net (code "62") (name "unconnected-(E2-SIGNAL-PadANT)") (class "Default")
      (node (ref "E2") (pin "ANT") (pinfunction "SIGNAL_ANT") (pintype "bidirectional"))
    )
    (net (code "63") (name "unconnected-(IC1-DIN2-Pad10)") (class "Default")
      (node (ref "IC1") (pin "10") (pinfunction "DIN2_10") (pintype "bidirectional"))
    )
    (net (code "64") (name "unconnected-(IC1-DOUT2-Pad7)") (class "Default")
      (node (ref "IC1") (pin "7") (pinfunction "DOUT2_7") (pintype "bidirectional"))
    )
    (net (code "65") (name "unconnected-(IC1-RIN2-Pad8)") (class "Default")
      (node (ref "IC1") (pin "8") (pinfunction "RIN2_8") (pintype "bidirectional"))
    )
    (net (code "66") (name "unconnected-(IC1-ROUT2-Pad9)") (class "Default")
      (node (ref "IC1") (pin "9") (pinfunction "ROUT2_9") (pintype "bidirectional"))
    )
    (net (code "67") (name "unconnected-(IC3-THERMAL_PAD-Pad21)") (class "Default")
      (node (ref "IC3") (pin "21") (pinfunction "THERMAL_PAD_21") (pintype "bidirectional"))
    )
    (net (code "68") (name "unconnected-(J2-Pad2)") (class "Default")
      (node (ref "J2") (pin "2") (pinfunction "2_2") (pintype "bidirectional"))
    )
    (net (code "69") (name "unconnected-(J2-Pad3)") (class "Default")
      (node (ref "J2") (pin "3") (pinfunction "3_3") (pintype "bidirectional"))
    )
    (net (code "70") (name "unconnected-(J2-Pad4)") (class "Default")
      (node (ref "J2") (pin "4") (pinfunction "4_4") (pintype "bidirectional"))
    )
    (net (code "71") (name "unconnected-(J2-Pad5)") (class "Default")
      (node (ref "J2") (pin "5") (pinfunction "5_5") (pintype "bidirectional"))
    )
    (net (code "72") (name "unconnected-(J2-Pad6)") (class "Default")
      (node (ref "J2") (pin "6") (pinfunction "6_6") (pintype "bidirectional"))
    )
    (net (code "73") (name "unconnected-(K1B-O-Pad1)") (class "Default")
      (node (ref "K1") (pin "1") (pinfunction "O_1") (pintype "passive"))
    )
    (net (code "74") (name "unconnected-(K1B-S-Pad10)") (class "Default")
      (node (ref "K1") (pin "10") (pinfunction "S_10") (pintype "passive"))
    )
    (net (code "75") (name "unconnected-(K2B-O-Pad1)") (class "Default")
      (node (ref "K2") (pin "1") (pinfunction "O_1") (pintype "passive"))
    )
    (net (code "76") (name "unconnected-(K2B-S-Pad10)") (class "Default")
      (node (ref "K2") (pin "10") (pinfunction "S_10") (pintype "passive"))
    )
    (net (code "77") (name "unconnected-(U1-(ADC0{slash}PCINT8)PC0-Pad23)") (class "Default")
      (node (ref "U1") (pin "23") (pinfunction "(ADC0/PCINT8)PC0_23") (pintype "bidirectional"))
    )
    (net (code "78") (name "unconnected-(U1-(ADC1{slash}PCINT9)PC1-Pad24)") (class "Default")
      (node (ref "U1") (pin "24") (pinfunction "(ADC1/PCINT9)PC1_24") (pintype "bidirectional"))
    )
    (net (code "79") (name "unconnected-(U1-(ADC2{slash}PCINT10)PC2-Pad25)") (class "Default")
      (node (ref "U1") (pin "25") (pinfunction "(ADC2/PCINT10)PC2_25") (pintype "bidirectional"))
    )
    (net (code "80") (name "unconnected-(U1-(ADC3{slash}PCINT11)PC3-Pad26)") (class "Default")
      (node (ref "U1") (pin "26") (pinfunction "(ADC3/PCINT11)PC3_26") (pintype "bidirectional"))
    )
    (net (code "81") (name "unconnected-(U1-(ADC4{slash}SDA{slash}PCINT12)PC4-Pad27)") (class "Default")
      (node (ref "U1") (pin "27") (pinfunction "(ADC4/SDA/PCINT12)PC4_27") (pintype "bidirectional"))
    )
    (net (code "82") (name "unconnected-(U1-(ADC5{slash}SCL{slash}PCINT13)PC5-Pad28)") (class "Default")
      (node (ref "U1") (pin "28") (pinfunction "(ADC5/SCL/PCINT13)PC5_28") (pintype "bidirectional"))
    )
    (net (code "83") (name "unconnected-(U1-(PCINT0{slash}CLKO{slash}ICP1)PB0-Pad12)") (class "Default")
      (node (ref "U1") (pin "12") (pinfunction "(PCINT0/CLKO/ICP1)PB0_12") (pintype "bidirectional"))
    )
    (net (code "84") (name "unconnected-(U1-(PCINT1{slash}OC1A)PB1-Pad13)") (class "Default")
      (node (ref "U1") (pin "13") (pinfunction "(PCINT1/OC1A)PB1_13") (pintype "bidirectional"))
    )
    (net (code "85") (name "unconnected-(U1-(PCINT2{slash}SS{slash}OC1B)PB2-Pad14)") (class "Default")
      (node (ref "U1") (pin "14") (pinfunction "(PCINT2/SS/OC1B)PB2_14") (pintype "bidirectional"))
    )
    (net (code "86") (name "unconnected-(U1-(PCINT3{slash}OC2A{slash}MOSI)PB3-Pad15)") (class "Default")
      (node (ref "U1") (pin "15") (pinfunction "(PCINT3/OC2A/MOSI)PB3_15") (pintype "bidirectional"))
    )
    (net (code "87") (name "unconnected-(U1-(PCINT4{slash}MISO)PB4-Pad16)") (class "Default")
      (node (ref "U1") (pin "16") (pinfunction "(PCINT4/MISO)PB4_16") (pintype "bidirectional"))
    )
    (net (code "88") (name "unconnected-(U1-(RESET{slash}PCINT14)PC6-Pad29)") (class "Default")
      (node (ref "U1") (pin "29") (pinfunction "(RESET/PCINT14)PC6_29") (pintype "bidirectional"))
    )
    (net (code "89") (name "unconnected-(U1-(SCK{slash}PCINT5)PB5-Pad17)") (class "Default")
      (node (ref "U1") (pin "17") (pinfunction "(SCK/PCINT5)PB5_17") (pintype "bidirectional"))
    )
    (net (code "90") (name "unconnected-(U1-ADC6-Pad19)") (class "Default")
      (node (ref "U1") (pin "19") (pinfunction "ADC6_19") (pintype "input"))
    )
    (net (code "91") (name "unconnected-(U1-ADC7-Pad22)") (class "Default")
      (node (ref "U1") (pin "22") (pinfunction "ADC7_22") (pintype "input"))
    )
    (net (code "92") (name "unconnected-(U1-PD0(RXD{slash}PCINT16)-Pad30)") (class "Default")
      (node (ref "U1") (pin "30") (pinfunction "PD0(RXD/PCINT16)_30") (pintype "bidirectional"))
    )
    (net (code "93") (name "unconnected-(U1-PD1(TXD{slash}PCINT17)-Pad31)") (class "Default")
      (node (ref "U1") (pin "31") (pinfunction "PD1(TXD/PCINT17)_31") (pintype "bidirectional"))
    )
    (net (code "94") (name "unconnected-(U1-PD2(INT0{slash}PCINT18)-Pad32)") (class "Default")
      (node (ref "U1") (pin "32") (pinfunction "PD2(INT0/PCINT18)_32") (pintype "bidirectional"))
    )
    (net (code "95") (name "unconnected-(U1-PD3(PCINT19{slash}OC2B{slash}INT1)-Pad1)") (class "Default")
      (node (ref "U1") (pin "1") (pinfunction "PD3(PCINT19/OC2B/INT1)_1") (pintype "bidirectional"))
    )
    (net (code "96") (name "unconnected-(U1-PD4(PCINT20{slash}XCK{slash}T0)-Pad2)") (class "Default")
      (node (ref "U1") (pin "2") (pinfunction "PD4(PCINT20/XCK/T0)_2") (pintype "bidirectional"))
    )
    (net (code "97") (name "unconnected-(U1-PD5(PCINT21{slash}OC0B{slash}T1)-Pad9)") (class "Default")
      (node (ref "U1") (pin "9") (pinfunction "PD5(PCINT21/OC0B/T1)_9") (pintype "bidirectional"))
    )
    (net (code "98") (name "unconnected-(U1-PD6(PCINT22{slash}OC0A{slash}AIN0)-Pad10)") (class "Default")
      (node (ref "U1") (pin "10") (pinfunction "PD6(PCINT22/OC0A/AIN0)_10") (pintype "bidirectional"))
    )
    (net (code "99") (name "unconnected-(U1-PD7(PCINT23{slash}AIN1)-Pad11)") (class "Default")
      (node (ref "U1") (pin "11") (pinfunction "PD7(PCINT23/AIN1)_11") (pintype "bidirectional"))
    )
    (net (code "100") (name "unconnected-(U2-(ADC1{slash}PCINT9)PC1-Pad24)") (class "Default")
      (node (ref "U2") (pin "24") (pinfunction "(ADC1/PCINT9)PC1_24") (pintype "bidirectional"))
    )
    (net (code "101") (name "unconnected-(U2-(ADC2{slash}PCINT10)PC2-Pad25)") (class "Default")
      (node (ref "U2") (pin "25") (pinfunction "(ADC2/PCINT10)PC2_25") (pintype "bidirectional"))
    )
    (net (code "102") (name "unconnected-(U2-(ADC3{slash}PCINT11)PC3-Pad26)") (class "Default")
      (node (ref "U2") (pin "26") (pinfunction "(ADC3/PCINT11)PC3_26") (pintype "bidirectional"))
    )
    (net (code "103") (name "unconnected-(U2-(PCINT2{slash}SS{slash}OC1B)PB2-Pad14)") (class "Default")
      (node (ref "U2") (pin "14") (pinfunction "(PCINT2/SS/OC1B)PB2_14") (pintype "bidirectional"))
    )
    (net (code "104") (name "unconnected-(U2-ADC6-Pad19)") (class "Default")
      (node (ref "U2") (pin "19") (pinfunction "ADC6_19") (pintype "input"))
    )
    (net (code "105") (name "unconnected-(U2-ADC7-Pad22)") (class "Default")
      (node (ref "U2") (pin "22") (pinfunction "ADC7_22") (pintype "input"))
    )
    (net (code "106") (name "unconnected-(U2-PD3(PCINT19{slash}OC2B{slash}INT1)-Pad1)") (class "Default")
      (node (ref "U2") (pin "1") (pinfunction "PD3(PCINT19/OC2B/INT1)_1") (pintype "bidirectional"))
    )
    (net (code "107") (name "unconnected-(U2-PD4(PCINT20{slash}XCK{slash}T0)-Pad2)") (class "Default")
      (node (ref "U2") (pin "2") (pinfunction "PD4(PCINT20/XCK/T0)_2") (pintype "bidirectional"))
    )
    (net (code "108") (name "unconnected-(X1A-KL-Pad1)") (class "Default")
      (node (ref "X1") (pin "1") (pinfunction "KL_1") (pintype "passive"))
    )
    (net (code "109") (name "unconnected-(X1B-KL-Pad10)") (class "Default")
      (node (ref "X1") (pin "10") (pinfunction "KL_10") (pintype "passive"))
    )
    (net (code "110") (name "unconnected-(X1E-KL-Pad4)") (class "Default")
      (node (ref "X1") (pin "4") (pinfunction "KL_4") (pintype "passive"))
    )
    (net (code "111") (name "unconnected-(X1G-KL-Pad6)") (class "Default")
      (node (ref "X1") (pin "6") (pinfunction "KL_6") (pintype "passive"))
    )
    (net (code "112") (name "unconnected-(X1H-KL-Pad7)") (class "Default")
      (node (ref "X1") (pin "7") (pinfunction "KL_7") (pintype "passive"))
    )
    (net (code "113") (name "unconnected-(X1I-KL-Pad8)") (class "Default")
      (node (ref "X1") (pin "8") (pinfunction "KL_8") (pintype "passive"))
    )
    (net (code "114") (name "unconnected-(X1J-KL-Pad9)") (class "Default")
      (node (ref "X1") (pin "9") (pinfunction "KL_9") (pintype "passive"))
    )
  )
)
